# HEADER_1.net
KiCad netlist of a schematic drawn in Altium Designer
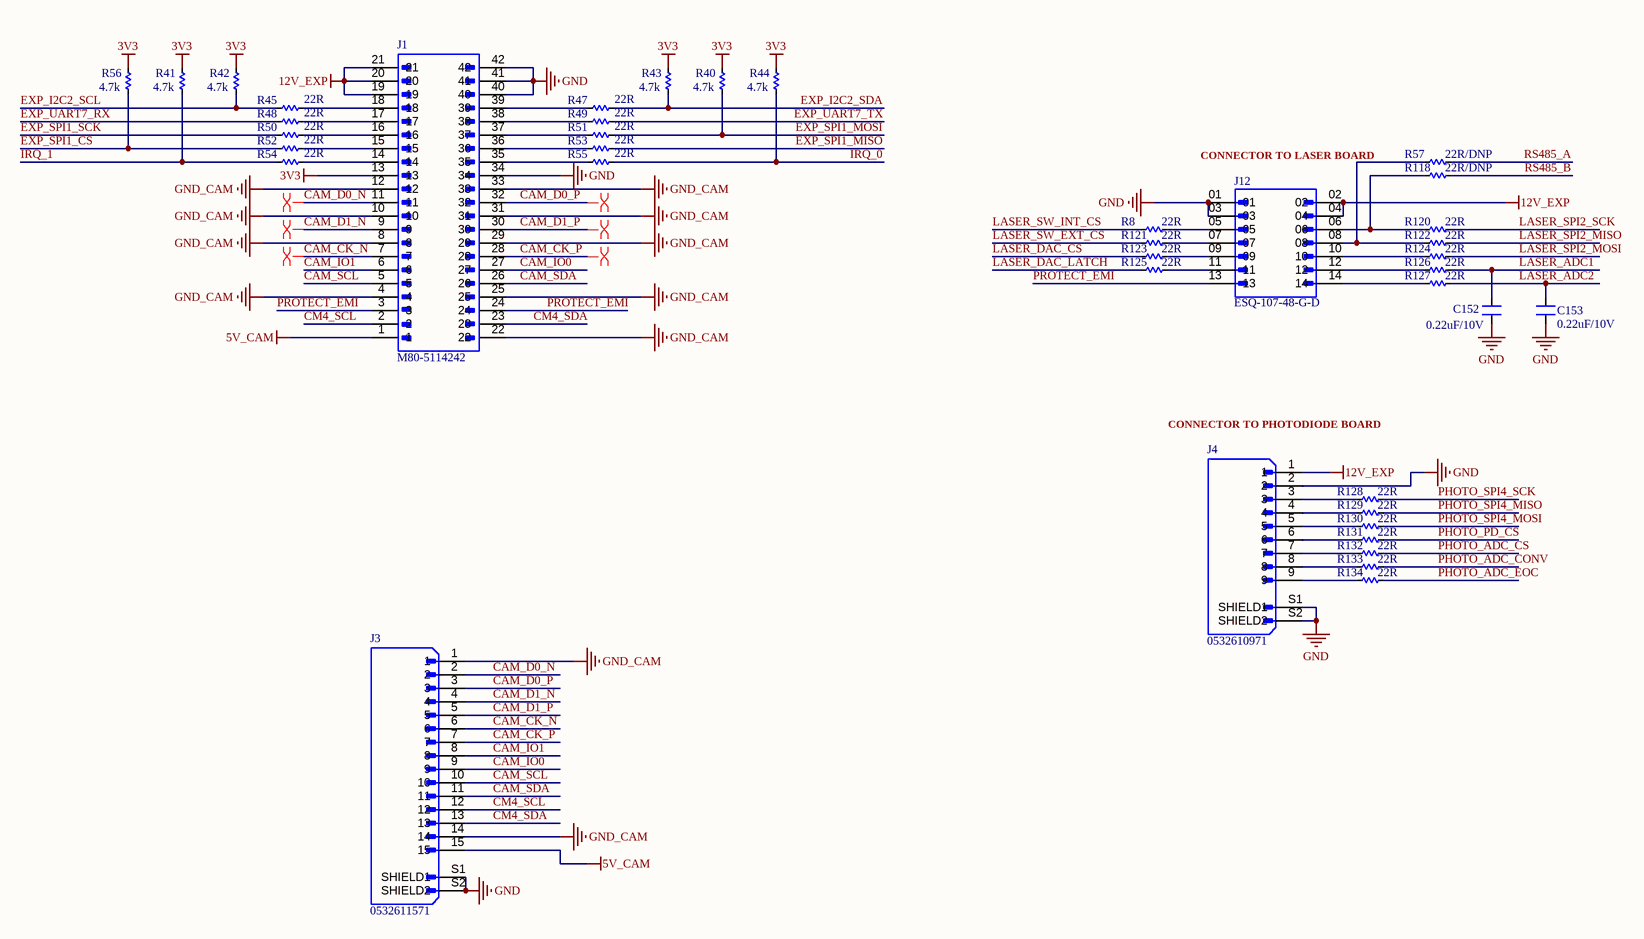
[diagram p0: HEADER_1.SchDoc]

(export (version "E")
  (design (tool "Eeschema 10.0.6"))
  (components
    (comp (ref "C152")
      (value "0.22uF/10V")
      (footprint "CAP_C_1608X80")
      (libsource (lib "EXP_HW_V3") (part "Capacitors"))
    )
    (comp (ref "C153")
      (value "0.22uF/10V")
      (footprint "CAP_C_1608X80")
      (libsource (lib "EXP_HW_V3") (part "Capacitors"))
    )
    (comp (ref "J1")
      (value "M80-5114242")
      (footprint "M80-5114242")
      (description "CONN HEADER VERT 42POS 2MM")
      (libsource (lib "EXP_HW_V2") (part "CONN_TH_42"))
    )
    (comp (ref "J3")
      (value "0532611571")
      (footprint "0532611571")
      (description "Conn Shrouded Header (4 Sides) HDR 15 POS 1.25mm Solder RA Side Entry SMD PicoBladeâ„¢ T/R")
      (fields (field (name "MP") "532611571") (field (name "MF") "Molex"))
      (libsource (lib "EXP_HW_V2") (part "CONN_SMD_15"))
    )
    (comp (ref "J4")
      (value "0532610971")
      (footprint "0532610971")
      (description "CONN HEADER SMD R/A 9POS 1.25MM")
      (libsource (lib "EXP_HW_V3") (part "CONN_SMD_09"))
    )
    (comp (ref "J12")
      (value "ESQ-107-48-G-D")
      (footprint "ESQ-107-37-G-D")
      (description "CONN SOCKET 14POS 0.1 GOLD PCB")
      (libsource (lib "EXP_HW_V2") (part "CONN_TH_14"))
    )
    (comp (ref "R8")
      (value "22R")
      (footprint "RES_C_1608X60")
      (description "SMD")
      (fields
        (field (name "MANUFACTURER") "Generic Components")
        (field (name "PUBLISHER") "Altium Hobart Technology Centre")
      )
      (libsource (lib "EXP_HW_V3") (part "Res SMD"))
    )
    (comp (ref "R40")
      (value "4.7k")
      (footprint "RES_C_1608X60")
      (description "SMD")
      (fields
        (field (name "MANUFACTURER") "Generic Components")
        (field (name "PUBLISHER") "Altium Hobart Technology Centre")
      )
      (libsource (lib "EXP_HW_V3") (part "Res SMD"))
    )
    (comp (ref "R41")
      (value "4.7k")
      (footprint "RES_C_1608X60")
      (description "SMD")
      (fields
        (field (name "MANUFACTURER") "Generic Components")
        (field (name "PUBLISHER") "Altium Hobart Technology Centre")
      )
      (libsource (lib "EXP_HW_V3") (part "Res SMD"))
    )
    (comp (ref "R42")
      (value "4.7k")
      (footprint "RES_C_1608X60")
      (description "SMD")
      (fields
        (field (name "MANUFACTURER") "Generic Components")
        (field (name "PUBLISHER") "Altium Hobart Technology Centre")
      )
      (libsource (lib "EXP_HW_V3") (part "Res SMD"))
    )
    (comp (ref "R43")
      (value "4.7k")
      (footprint "RES_C_1608X60")
      (description "SMD")
      (fields
        (field (name "MANUFACTURER") "Generic Components")
        (field (name "PUBLISHER") "Altium Hobart Technology Centre")
      )
      (libsource (lib "EXP_HW_V3") (part "Res SMD"))
    )
    (comp (ref "R44")
      (value "4.7k")
      (footprint "RES_C_1608X60")
      (description "SMD")
      (fields
        (field (name "MANUFACTURER") "Generic Components")
        (field (name "PUBLISHER") "Altium Hobart Technology Centre")
      )
      (libsource (lib "EXP_HW_V3") (part "Res SMD"))
    )
    (comp (ref "R45")
      (value "22R")
      (footprint "RES_C_1608X60")
      (description "SMD")
      (fields
        (field (name "MANUFACTURER") "Generic Components")
        (field (name "PUBLISHER") "Altium Hobart Technology Centre")
      )
      (libsource (lib "EXP_HW_V3") (part "Res SMD"))
    )
    (comp (ref "R47")
      (value "22R")
      (footprint "RES_C_1608X60")
      (description "SMD")
      (fields
        (field (name "MANUFACTURER") "Generic Components")
        (field (name "PUBLISHER") "Altium Hobart Technology Centre")
      )
      (libsource (lib "EXP_HW_V3") (part "Res SMD"))
    )
    (comp (ref "R48")
      (value "22R")
      (footprint "RES_C_1608X60")
      (description "SMD")
      (fields
        (field (name "MANUFACTURER") "Generic Components")
        (field (name "PUBLISHER") "Altium Hobart Technology Centre")
      )
      (libsource (lib "EXP_HW_V3") (part "Res SMD"))
    )
    (comp (ref "R49")
      (value "22R")
      (footprint "RES_C_1608X60")
      (description "SMD")
      (fields
        (field (name "MANUFACTURER") "Generic Components")
        (field (name "PUBLISHER") "Altium Hobart Technology Centre")
      )
      (libsource (lib "EXP_HW_V3") (part "Res SMD"))
    )
    (comp (ref "R50")
      (value "22R")
      (footprint "RES_C_1608X60")
      (description "SMD")
      (fields
        (field (name "MANUFACTURER") "Generic Components")
        (field (name "PUBLISHER") "Altium Hobart Technology Centre")
      )
      (libsource (lib "EXP_HW_V3") (part "Res SMD"))
    )
    (comp (ref "R51")
      (value "22R")
      (footprint "RES_C_1608X60")
      (description "SMD")
      (fields
        (field (name "MANUFACTURER") "Generic Components")
        (field (name "PUBLISHER") "Altium Hobart Technology Centre")
      )
      (libsource (lib "EXP_HW_V3") (part "Res SMD"))
    )
    (comp (ref "R52")
      (value "22R")
      (footprint "RES_C_1608X60")
      (description "SMD")
      (fields
        (field (name "MANUFACTURER") "Generic Components")
        (field (name "PUBLISHER") "Altium Hobart Technology Centre")
      )
      (libsource (lib "EXP_HW_V3") (part "Res SMD"))
    )
    (comp (ref "R53")
      (value "22R")
      (footprint "RES_C_1608X60")
      (description "SMD")
      (fields
        (field (name "MANUFACTURER") "Generic Components")
        (field (name "PUBLISHER") "Altium Hobart Technology Centre")
      )
      (libsource (lib "EXP_HW_V3") (part "Res SMD"))
    )
    (comp (ref "R54")
      (value "22R")
      (footprint "RES_C_1608X60")
      (description "SMD")
      (fields
        (field (name "MANUFACTURER") "Generic Components")
        (field (name "PUBLISHER") "Altium Hobart Technology Centre")
      )
      (libsource (lib "EXP_HW_V3") (part "Res SMD"))
    )
    (comp (ref "R55")
      (value "22R")
      (footprint "RES_C_1608X60")
      (description "SMD")
      (fields
        (field (name "MANUFACTURER") "Generic Components")
        (field (name "PUBLISHER") "Altium Hobart Technology Centre")
      )
      (libsource (lib "EXP_HW_V3") (part "Res SMD"))
    )
    (comp (ref "R56")
      (value "4.7k")
      (footprint "RES_C_1608X60")
      (description "SMD")
      (fields
        (field (name "MANUFACTURER") "Generic Components")
        (field (name "PUBLISHER") "Altium Hobart Technology Centre")
      )
      (libsource (lib "EXP_HW_V3") (part "Res SMD"))
    )
    (comp (ref "R57")
      (value "22R/DNP")
      (footprint "RES_C_1608X60")
      (description "SMD")
      (fields
        (field (name "MANUFACTURER") "Generic Components")
        (field (name "PUBLISHER") "Altium Hobart Technology Centre")
      )
      (libsource (lib "EXP_HW_V3") (part "Res SMD"))
    )
    (comp (ref "R118")
      (value "22R/DNP")
      (footprint "RES_C_1608X60")
      (description "SMD")
      (fields
        (field (name "MANUFACTURER") "Generic Components")
        (field (name "PUBLISHER") "Altium Hobart Technology Centre")
      )
      (libsource (lib "EXP_HW_V3") (part "Res SMD"))
    )
    (comp (ref "R120")
      (value "22R")
      (footprint "RES_C_1608X60")
      (description "SMD")
      (fields
        (field (name "MANUFACTURER") "Generic Components")
        (field (name "PUBLISHER") "Altium Hobart Technology Centre")
      )
      (libsource (lib "EXP_HW_V3") (part "Res SMD"))
    )
    (comp (ref "R121")
      (value "22R")
      (footprint "RES_C_1608X60")
      (description "SMD")
      (fields
        (field (name "MANUFACTURER") "Generic Components")
        (field (name "PUBLISHER") "Altium Hobart Technology Centre")
      )
      (libsource (lib "EXP_HW_V3") (part "Res SMD"))
    )
    (comp (ref "R122")
      (value "22R")
      (footprint "RES_C_1608X60")
      (description "SMD")
      (fields
        (field (name "MANUFACTURER") "Generic Components")
        (field (name "PUBLISHER") "Altium Hobart Technology Centre")
      )
      (libsource (lib "EXP_HW_V3") (part "Res SMD"))
    )
    (comp (ref "R123")
      (value "22R")
      (footprint "RES_C_1608X60")
      (description "SMD")
      (fields
        (field (name "MANUFACTURER") "Generic Components")
        (field (name "PUBLISHER") "Altium Hobart Technology Centre")
      )
      (libsource (lib "EXP_HW_V3") (part "Res SMD"))
    )
    (comp (ref "R124")
      (value "22R")
      (footprint "RES_C_1608X60")
      (description "SMD")
      (fields
        (field (name "MANUFACTURER") "Generic Components")
        (field (name "PUBLISHER") "Altium Hobart Technology Centre")
      )
      (libsource (lib "EXP_HW_V3") (part "Res SMD"))
    )
    (comp (ref "R125")
      (value "22R")
      (footprint "RES_C_1608X60")
      (description "SMD")
      (fields
        (field (name "MANUFACTURER") "Generic Components")
        (field (name "PUBLISHER") "Altium Hobart Technology Centre")
      )
      (libsource (lib "EXP_HW_V3") (part "Res SMD"))
    )
    (comp (ref "R126")
      (value "22R")
      (footprint "RES_C_1608X60")
      (description "SMD")
      (fields
        (field (name "MANUFACTURER") "Generic Components")
        (field (name "PUBLISHER") "Altium Hobart Technology Centre")
      )
      (libsource (lib "EXP_HW_V3") (part "Res SMD"))
    )
    (comp (ref "R127")
      (value "22R")
      (footprint "RES_C_1608X60")
      (description "SMD")
      (fields
        (field (name "MANUFACTURER") "Generic Components")
        (field (name "PUBLISHER") "Altium Hobart Technology Centre")
      )
      (libsource (lib "EXP_HW_V3") (part "Res SMD"))
    )
    (comp (ref "R128")
      (value "22R")
      (footprint "RES_C_1608X60")
      (description "SMD")
      (fields
        (field (name "MANUFACTURER") "Generic Components")
        (field (name "PUBLISHER") "Altium Hobart Technology Centre")
      )
      (libsource (lib "EXP_HW_V3") (part "Res SMD"))
    )
    (comp (ref "R129")
      (value "22R")
      (footprint "RES_C_1608X60")
      (description "SMD")
      (fields
        (field (name "MANUFACTURER") "Generic Components")
        (field (name "PUBLISHER") "Altium Hobart Technology Centre")
      )
      (libsource (lib "EXP_HW_V3") (part "Res SMD"))
    )
    (comp (ref "R130")
      (value "22R")
      (footprint "RES_C_1608X60")
      (description "SMD")
      (fields
        (field (name "MANUFACTURER") "Generic Components")
        (field (name "PUBLISHER") "Altium Hobart Technology Centre")
      )
      (libsource (lib "EXP_HW_V3") (part "Res SMD"))
    )
    (comp (ref "R131")
      (value "22R")
      (footprint "RES_C_1608X60")
      (description "SMD")
      (fields
        (field (name "MANUFACTURER") "Generic Components")
        (field (name "PUBLISHER") "Altium Hobart Technology Centre")
      )
      (libsource (lib "EXP_HW_V3") (part "Res SMD"))
    )
    (comp (ref "R132")
      (value "22R")
      (footprint "RES_C_1608X60")
      (description "SMD")
      (fields
        (field (name "MANUFACTURER") "Generic Components")
        (field (name "PUBLISHER") "Altium Hobart Technology Centre")
      )
      (libsource (lib "EXP_HW_V3") (part "Res SMD"))
    )
    (comp (ref "R133")
      (value "22R")
      (footprint "RES_C_1608X60")
      (description "SMD")
      (fields
        (field (name "MANUFACTURER") "Generic Components")
        (field (name "PUBLISHER") "Altium Hobart Technology Centre")
      )
      (libsource (lib "EXP_HW_V3") (part "Res SMD"))
    )
    (comp (ref "R134")
      (value "22R")
      (footprint "RES_C_1608X60")
      (description "SMD")
      (fields
        (field (name "MANUFACTURER") "Generic Components")
        (field (name "PUBLISHER") "Altium Hobart Technology Centre")
      )
      (libsource (lib "EXP_HW_V3") (part "Res SMD"))
    )
  )
  (nets
    (net (code "1") (name "/CAM_CK_N") (class "Default")
      (node (ref "J1") (pin "7") (pinfunction "7_7") (pintype "passive"))
      (node (ref "J3") (pin "6") (pinfunction "6_6") (pintype "passive"))
    )
    (net (code "2") (name "/CAM_CK_P") (class "Default")
      (node (ref "J1") (pin "28") (pinfunction "28_28") (pintype "passive"))
      (node (ref "J3") (pin "7") (pinfunction "7_7") (pintype "passive"))
    )
    (net (code "3") (name "/CAM_D0_N") (class "Default")
      (node (ref "J1") (pin "11") (pinfunction "11_11") (pintype "passive"))
      (node (ref "J3") (pin "2") (pinfunction "2_2") (pintype "passive"))
    )
    (net (code "4") (name "/CAM_D0_P") (class "Default")
      (node (ref "J1") (pin "32") (pinfunction "32_32") (pintype "passive"))
      (node (ref "J3") (pin "3") (pinfunction "3_3") (pintype "passive"))
    )
    (net (code "5") (name "/CAM_D1_N") (class "Default")
      (node (ref "J1") (pin "9") (pinfunction "9_9") (pintype "passive"))
      (node (ref "J3") (pin "4") (pinfunction "4_4") (pintype "passive"))
    )
    (net (code "6") (name "/CAM_D1_P") (class "Default")
      (node (ref "J1") (pin "30") (pinfunction "30_30") (pintype "passive"))
      (node (ref "J3") (pin "5") (pinfunction "5_5") (pintype "passive"))
    )
    (net (code "7") (name "/CAM_IO0") (class "Default")
      (node (ref "J1") (pin "27") (pinfunction "27_27") (pintype "passive"))
      (node (ref "J3") (pin "9") (pinfunction "9_9") (pintype "passive"))
    )
    (net (code "8") (name "/CAM_IO1") (class "Default")
      (node (ref "J1") (pin "6") (pinfunction "6_6") (pintype "passive"))
      (node (ref "J3") (pin "8") (pinfunction "8_8") (pintype "passive"))
    )
    (net (code "9") (name "/CAM_SCL") (class "Default")
      (node (ref "J1") (pin "5") (pinfunction "5_5") (pintype "passive"))
      (node (ref "J3") (pin "10") (pinfunction "10_10") (pintype "passive"))
    )
    (net (code "10") (name "/CAM_SDA") (class "Default")
      (node (ref "J1") (pin "26") (pinfunction "26_26") (pintype "passive"))
      (node (ref "J3") (pin "11") (pinfunction "11_11") (pintype "passive"))
    )
    (net (code "11") (name "/CM4_SCL") (class "Default")
      (node (ref "J1") (pin "2") (pinfunction "2_2") (pintype "passive"))
      (node (ref "J3") (pin "12") (pinfunction "12_12") (pintype "passive"))
    )
    (net (code "12") (name "/CM4_SDA") (class "Default")
      (node (ref "J1") (pin "23") (pinfunction "23_23") (pintype "passive"))
      (node (ref "J3") (pin "13") (pinfunction "13_13") (pintype "passive"))
    )
    (net (code "13") (name "/EXP_I2C2_SCL") (class "Default")
      (node (ref "R42") (pin "2") (pinfunction "2_2") (pintype "passive"))
      (node (ref "R45") (pin "1") (pinfunction "1_1") (pintype "passive"))
    )
    (net (code "14") (name "/EXP_I2C2_SDA") (class "Default")
      (node (ref "R43") (pin "2") (pinfunction "2_2") (pintype "passive"))
      (node (ref "R47") (pin "2") (pinfunction "2_2") (pintype "passive"))
    )
    (net (code "15") (name "/EXP_SPI1_CS") (class "Default")
      (node (ref "R52") (pin "1") (pinfunction "1_1") (pintype "passive"))
      (node (ref "R56") (pin "2") (pinfunction "2_2") (pintype "passive"))
    )
    (net (code "16") (name "/EXP_SPI1_MISO") (class "Default")
      (node (ref "R53") (pin "2") (pinfunction "2_2") (pintype "passive"))
    )
    (net (code "17") (name "/EXP_SPI1_MOSI") (class "Default")
      (node (ref "R40") (pin "2") (pinfunction "2_2") (pintype "passive"))
      (node (ref "R51") (pin "2") (pinfunction "2_2") (pintype "passive"))
    )
    (net (code "18") (name "/EXP_SPI1_SCK") (class "Default")
      (node (ref "R50") (pin "1") (pinfunction "1_1") (pintype "passive"))
    )
    (net (code "19") (name "/EXP_UART7_RX") (class "Default")
      (node (ref "R48") (pin "1") (pinfunction "1_1") (pintype "passive"))
    )
    (net (code "20") (name "/EXP_UART7_TX") (class "Default")
      (node (ref "R49") (pin "2") (pinfunction "2_2") (pintype "passive"))
    )
    (net (code "21") (name "/IRQ_0") (class "Default")
      (node (ref "R44") (pin "2") (pinfunction "2_2") (pintype "passive"))
      (node (ref "R55") (pin "2") (pinfunction "2_2") (pintype "passive"))
    )
    (net (code "22") (name "/IRQ_1") (class "Default")
      (node (ref "R41") (pin "2") (pinfunction "2_2") (pintype "passive"))
      (node (ref "R54") (pin "1") (pinfunction "1_1") (pintype "passive"))
    )
    (net (code "23") (name "/LASER_ADC1") (class "Default")
      (node (ref "C152") (pin "2") (pinfunction "2_2") (pintype "passive"))
      (node (ref "R126") (pin "2") (pinfunction "2_2") (pintype "passive"))
    )
    (net (code "24") (name "/LASER_ADC2") (class "Default")
      (node (ref "C153") (pin "2") (pinfunction "2_2") (pintype "passive"))
      (node (ref "R127") (pin "2") (pinfunction "2_2") (pintype "passive"))
    )
    (net (code "25") (name "/LASER_DAC_CS") (class "Default")
      (node (ref "R123") (pin "1") (pinfunction "1_1") (pintype "passive"))
    )
    (net (code "26") (name "/LASER_DAC_LATCH") (class "Default")
      (node (ref "R125") (pin "1") (pinfunction "1_1") (pintype "passive"))
    )
    (net (code "27") (name "/LASER_SPI2_MISO") (class "Default")
      (node (ref "R122") (pin "2") (pinfunction "2_2") (pintype "passive"))
    )
    (net (code "28") (name "/LASER_SPI2_MOSI") (class "Default")
      (node (ref "R124") (pin "2") (pinfunction "2_2") (pintype "passive"))
    )
    (net (code "29") (name "/LASER_SPI2_SCK") (class "Default")
      (node (ref "R120") (pin "2") (pinfunction "2_2") (pintype "passive"))
    )
    (net (code "30") (name "/LASER_SW_EXT_CS") (class "Default")
      (node (ref "R121") (pin "1") (pinfunction "1_1") (pintype "passive"))
    )
    (net (code "31") (name "/LASER_SW_INT_CS") (class "Default")
      (node (ref "R8") (pin "1") (pinfunction "1_1") (pintype "passive"))
    )
    (net (code "32") (name "/PHOTO_ADC_CONV") (class "Default")
      (node (ref "R133") (pin "2") (pinfunction "2_2") (pintype "passive"))
    )
    (net (code "33") (name "/PHOTO_ADC_CS") (class "Default")
      (node (ref "R132") (pin "2") (pinfunction "2_2") (pintype "passive"))
    )
    (net (code "34") (name "/PHOTO_ADC_EOC") (class "Default")
      (node (ref "R134") (pin "2") (pinfunction "2_2") (pintype "passive"))
    )
    (net (code "35") (name "/PHOTO_PD_CS") (class "Default")
      (node (ref "R131") (pin "2") (pinfunction "2_2") (pintype "passive"))
    )
    (net (code "36") (name "/PHOTO_SPI4_MISO") (class "Default")
      (node (ref "R129") (pin "2") (pinfunction "2_2") (pintype "passive"))
    )
    (net (code "37") (name "/PHOTO_SPI4_MOSI") (class "Default")
      (node (ref "R130") (pin "2") (pinfunction "2_2") (pintype "passive"))
    )
    (net (code "38") (name "/PHOTO_SPI4_SCK") (class "Default")
      (node (ref "R128") (pin "2") (pinfunction "2_2") (pintype "passive"))
    )
    (net (code "39") (name "/PROTECT_EMI") (class "Default")
      (node (ref "J1") (pin "24") (pinfunction "24_24") (pintype "passive"))
      (node (ref "J1") (pin "3") (pinfunction "3_3") (pintype "passive"))
      (node (ref "J12") (pin "13") (pinfunction "13_13") (pintype "passive"))
    )
    (net (code "40") (name "/RS485_A") (class "Default")
      (node (ref "R57") (pin "2") (pinfunction "2_2") (pintype "passive"))
    )
    (net (code "41") (name "/RS485_B") (class "Default")
      (node (ref "R118") (pin "2") (pinfunction "2_2") (pintype "passive"))
    )
    (net (code "42") (name "3V3") (class "Default")
      (node (ref "J1") (pin "13") (pinfunction "13_13") (pintype "passive"))
      (node (ref "R40") (pin "1") (pinfunction "1_1") (pintype "passive"))
      (node (ref "R41") (pin "1") (pinfunction "1_1") (pintype "passive"))
      (node (ref "R42") (pin "1") (pinfunction "1_1") (pintype "passive"))
      (node (ref "R43") (pin "1") (pinfunction "1_1") (pintype "passive"))
      (node (ref "R44") (pin "1") (pinfunction "1_1") (pintype "passive"))
      (node (ref "R56") (pin "1") (pinfunction "1_1") (pintype "passive"))
    )
    (net (code "43") (name "5V_CAM") (class "Default")
      (node (ref "J1") (pin "1") (pinfunction "1_1") (pintype "passive"))
      (node (ref "J3") (pin "15") (pinfunction "15_15") (pintype "passive"))
    )
    (net (code "44") (name "12V_EXP") (class "Default")
      (node (ref "J1") (pin "19") (pinfunction "19_19") (pintype "passive"))
      (node (ref "J1") (pin "20") (pinfunction "20_20") (pintype "passive"))
      (node (ref "J1") (pin "21") (pinfunction "21_21") (pintype "passive"))
      (node (ref "J12") (pin "02") (pinfunction "02_02") (pintype "passive"))
      (node (ref "J12") (pin "04") (pinfunction "04_04") (pintype "passive"))
      (node (ref "J4") (pin "1") (pinfunction "1_1") (pintype "passive"))
    )
    (net (code "45") (name "GND") (class "Default")
      (node (ref "C152") (pin "1") (pinfunction "1_1") (pintype "passive"))
      (node (ref "C153") (pin "1") (pinfunction "1_1") (pintype "passive"))
      (node (ref "J1") (pin "34") (pinfunction "34_34") (pintype "passive"))
      (node (ref "J1") (pin "40") (pinfunction "40_40") (pintype "passive"))
      (node (ref "J1") (pin "41") (pinfunction "41_41") (pintype "passive"))
      (node (ref "J1") (pin "42") (pinfunction "42_42") (pintype "passive"))
      (node (ref "J12") (pin "01") (pinfunction "01_01") (pintype "passive"))
      (node (ref "J12") (pin "03") (pinfunction "03_03") (pintype "passive"))
      (node (ref "J3") (pin "S1") (pinfunction "SHIELD1_S1") (pintype "passive"))
      (node (ref "J3") (pin "S2") (pinfunction "SHIELD2_S2") (pintype "passive"))
      (node (ref "J4") (pin "2") (pinfunction "2_2") (pintype "passive"))
      (node (ref "J4") (pin "S1") (pinfunction "SHIELD1_S1") (pintype "passive"))
      (node (ref "J4") (pin "S2") (pinfunction "SHIELD2_S2") (pintype "passive"))
    )
    (net (code "46") (name "GND_CAM") (class "Default")
      (node (ref "J1") (pin "10") (pinfunction "10_10") (pintype "passive"))
      (node (ref "J1") (pin "12") (pinfunction "12_12") (pintype "passive"))
      (node (ref "J1") (pin "22") (pinfunction "22_22") (pintype "passive"))
      (node (ref "J1") (pin "25") (pinfunction "25_25") (pintype "passive"))
      (node (ref "J1") (pin "29") (pinfunction "29_29") (pintype "passive"))
      (node (ref "J1") (pin "31") (pinfunction "31_31") (pintype "passive"))
      (node (ref "J1") (pin "33") (pinfunction "33_33") (pintype "passive"))
      (node (ref "J1") (pin "4") (pinfunction "4_4") (pintype "passive"))
      (node (ref "J1") (pin "8") (pinfunction "8_8") (pintype "passive"))
      (node (ref "J3") (pin "1") (pinfunction "1_1") (pintype "passive"))
      (node (ref "J3") (pin "14") (pinfunction "14_14") (pintype "passive"))
    )
    (net (code "47") (name "Net-(J1-Pad14)") (class "Default")
      (node (ref "J1") (pin "14") (pinfunction "14_14") (pintype "passive"))
      (node (ref "R54") (pin "2") (pinfunction "2_2") (pintype "passive"))
    )
    (net (code "48") (name "Net-(J1-Pad15)") (class "Default")
      (node (ref "J1") (pin "15") (pinfunction "15_15") (pintype "passive"))
      (node (ref "R52") (pin "2") (pinfunction "2_2") (pintype "passive"))
    )
    (net (code "49") (name "Net-(J1-Pad16)") (class "Default")
      (node (ref "J1") (pin "16") (pinfunction "16_16") (pintype "passive"))
      (node (ref "R50") (pin "2") (pinfunction "2_2") (pintype "passive"))
    )
    (net (code "50") (name "Net-(J1-Pad17)") (class "Default")
      (node (ref "J1") (pin "17") (pinfunction "17_17") (pintype "passive"))
      (node (ref "R48") (pin "2") (pinfunction "2_2") (pintype "passive"))
    )
    (net (code "51") (name "Net-(J1-Pad18)") (class "Default")
      (node (ref "J1") (pin "18") (pinfunction "18_18") (pintype "passive"))
      (node (ref "R45") (pin "2") (pinfunction "2_2") (pintype "passive"))
    )
    (net (code "52") (name "Net-(J1-Pad35)") (class "Default")
      (node (ref "J1") (pin "35") (pinfunction "35_35") (pintype "passive"))
      (node (ref "R55") (pin "1") (pinfunction "1_1") (pintype "passive"))
    )
    (net (code "53") (name "Net-(J1-Pad36)") (class "Default")
      (node (ref "J1") (pin "36") (pinfunction "36_36") (pintype "passive"))
      (node (ref "R53") (pin "1") (pinfunction "1_1") (pintype "passive"))
    )
    (net (code "54") (name "Net-(J1-Pad37)") (class "Default")
      (node (ref "J1") (pin "37") (pinfunction "37_37") (pintype "passive"))
      (node (ref "R51") (pin "1") (pinfunction "1_1") (pintype "passive"))
    )
    (net (code "55") (name "Net-(J1-Pad38)") (class "Default")
      (node (ref "J1") (pin "38") (pinfunction "38_38") (pintype "passive"))
      (node (ref "R49") (pin "1") (pinfunction "1_1") (pintype "passive"))
    )
    (net (code "56") (name "Net-(J1-Pad39)") (class "Default")
      (node (ref "J1") (pin "39") (pinfunction "39_39") (pintype "passive"))
      (node (ref "R47") (pin "1") (pinfunction "1_1") (pintype "passive"))
    )
    (net (code "57") (name "Net-(J4-Pad3)") (class "Default")
      (node (ref "J4") (pin "3") (pinfunction "3_3") (pintype "passive"))
      (node (ref "R128") (pin "1") (pinfunction "1_1") (pintype "passive"))
    )
    (net (code "58") (name "Net-(J4-Pad4)") (class "Default")
      (node (ref "J4") (pin "4") (pinfunction "4_4") (pintype "passive"))
      (node (ref "R129") (pin "1") (pinfunction "1_1") (pintype "passive"))
    )
    (net (code "59") (name "Net-(J4-Pad5)") (class "Default")
      (node (ref "J4") (pin "5") (pinfunction "5_5") (pintype "passive"))
      (node (ref "R130") (pin "1") (pinfunction "1_1") (pintype "passive"))
    )
    (net (code "60") (name "Net-(J4-Pad6)") (class "Default")
      (node (ref "J4") (pin "6") (pinfunction "6_6") (pintype "passive"))
      (node (ref "R131") (pin "1") (pinfunction "1_1") (pintype "passive"))
    )
    (net (code "61") (name "Net-(J4-Pad7)") (class "Default")
      (node (ref "J4") (pin "7") (pinfunction "7_7") (pintype "passive"))
      (node (ref "R132") (pin "1") (pinfunction "1_1") (pintype "passive"))
    )
    (net (code "62") (name "Net-(J4-Pad8)") (class "Default")
      (node (ref "J4") (pin "8") (pinfunction "8_8") (pintype "passive"))
      (node (ref "R133") (pin "1") (pinfunction "1_1") (pintype "passive"))
    )
    (net (code "63") (name "Net-(J4-Pad9)") (class "Default")
      (node (ref "J4") (pin "9") (pinfunction "9_9") (pintype "passive"))
      (node (ref "R134") (pin "1") (pinfunction "1_1") (pintype "passive"))
    )
    (net (code "64") (name "Net-(J12-Pad05)") (class "Default")
      (node (ref "J12") (pin "05") (pinfunction "05_05") (pintype "passive"))
      (node (ref "R8") (pin "2") (pinfunction "2_2") (pintype "passive"))
    )
    (net (code "65") (name "Net-(J12-Pad06)") (class "Default")
      (node (ref "J12") (pin "06") (pinfunction "06_06") (pintype "passive"))
      (node (ref "R118") (pin "1") (pinfunction "1_1") (pintype "passive"))
      (node (ref "R120") (pin "1") (pinfunction "1_1") (pintype "passive"))
    )
    (net (code "66") (name "Net-(J12-Pad07)") (class "Default")
      (node (ref "J12") (pin "07") (pinfunction "07_07") (pintype "passive"))
      (node (ref "R121") (pin "2") (pinfunction "2_2") (pintype "passive"))
    )
    (net (code "67") (name "Net-(J12-Pad08)") (class "Default")
      (node (ref "J12") (pin "08") (pinfunction "08_08") (pintype "passive"))
      (node (ref "R122") (pin "1") (pinfunction "1_1") (pintype "passive"))
      (node (ref "R57") (pin "1") (pinfunction "1_1") (pintype "passive"))
    )
    (net (code "68") (name "Net-(J12-Pad09)") (class "Default")
      (node (ref "J12") (pin "09") (pinfunction "09_09") (pintype "passive"))
      (node (ref "R123") (pin "2") (pinfunction "2_2") (pintype "passive"))
    )
    (net (code "69") (name "Net-(J12-Pad10)") (class "Default")
      (node (ref "J12") (pin "10") (pinfunction "10_10") (pintype "passive"))
      (node (ref "R124") (pin "1") (pinfunction "1_1") (pintype "passive"))
    )
    (net (code "70") (name "Net-(J12-Pad11)") (class "Default")
      (node (ref "J12") (pin "11") (pinfunction "11_11") (pintype "passive"))
      (node (ref "R125") (pin "2") (pinfunction "2_2") (pintype "passive"))
    )
    (net (code "71") (name "Net-(J12-Pad12)") (class "Default")
      (node (ref "J12") (pin "12") (pinfunction "12_12") (pintype "passive"))
      (node (ref "R126") (pin "1") (pinfunction "1_1") (pintype "passive"))
    )
    (net (code "72") (name "Net-(J12-Pad14)") (class "Default")
      (node (ref "J12") (pin "14") (pinfunction "14_14") (pintype "passive"))
      (node (ref "R127") (pin "1") (pinfunction "1_1") (pintype "passive"))
    )
  )
)
